# board-forblock.net
KiCad netlist of a schematic drawn in EAGLE
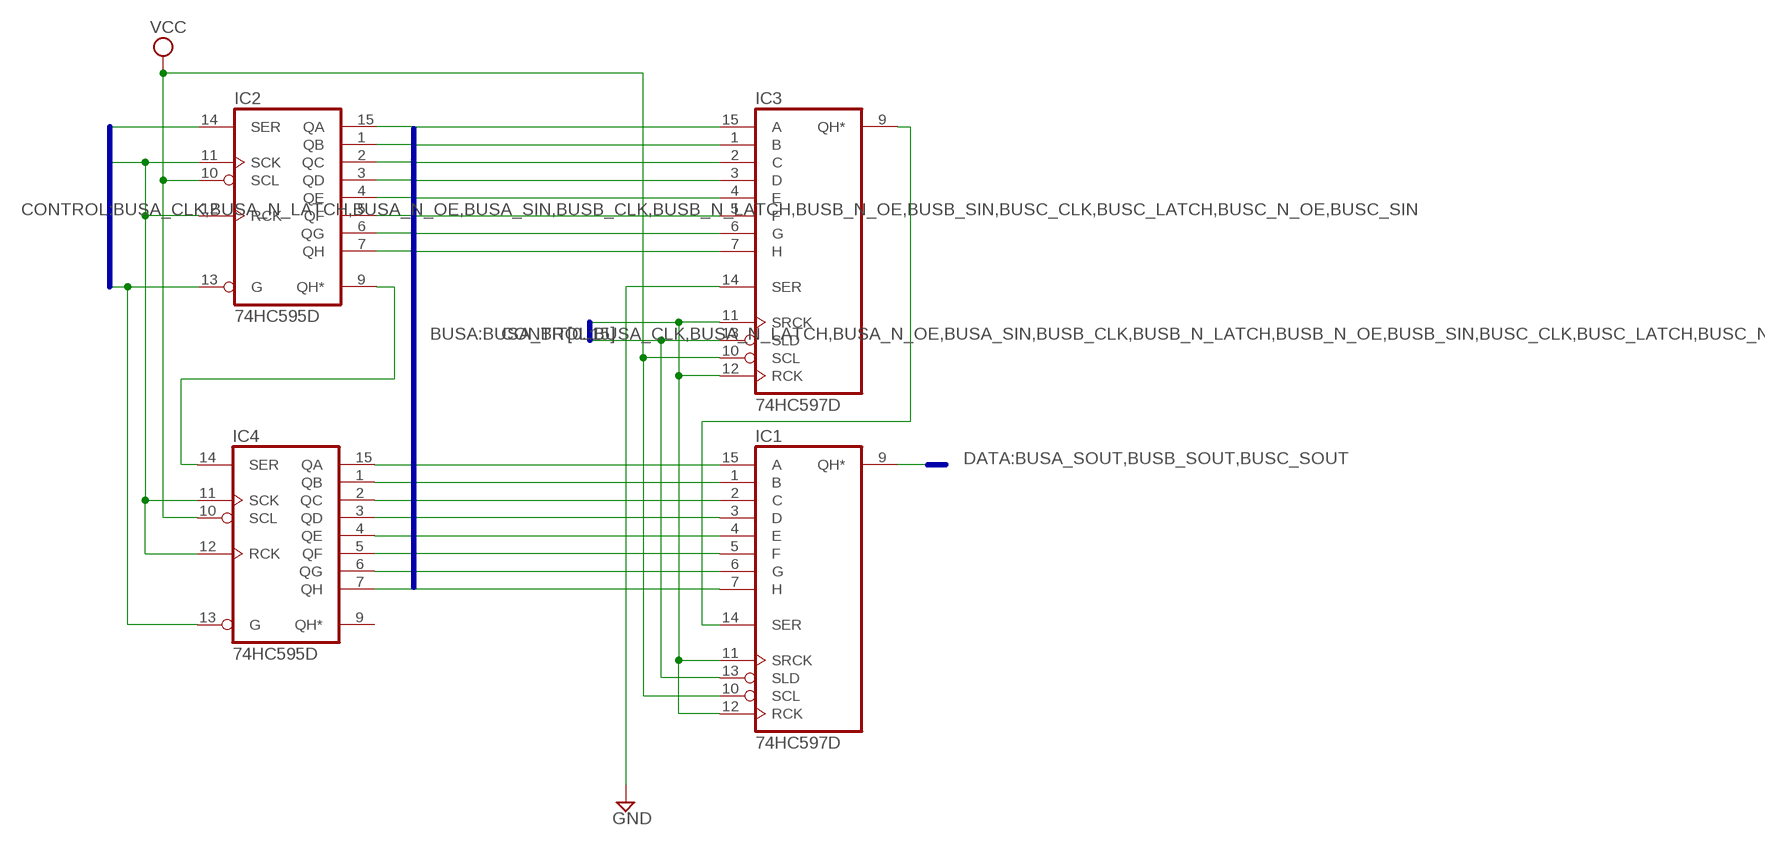
[diagram p0: schematic, sheet 1]

(export (version "E")
  (design (tool "Eeschema 10.0.6"))
  (components
    (comp (ref "IC1")
      (value "74HC597D")
      (footprint "eagle-import:SO16")
      (libsource (lib "eagle-import") (part "74597DHC"))
    )
    (comp (ref "IC2")
      (value "74HC595D")
      (footprint "eagle-import:SO16")
      (libsource (lib "eagle-import") (part "74595DHC"))
    )
    (comp (ref "IC3")
      (value "74HC597D")
      (footprint "eagle-import:SO16")
      (libsource (lib "eagle-import") (part "74597DHC"))
    )
    (comp (ref "IC4")
      (value "74HC595D")
      (footprint "eagle-import:SO16")
      (libsource (lib "eagle-import") (part "74595DHC"))
    )
  )
  (nets
    (net (code "33") (name "/BUSA_BIT0") (class "Default")
      (node (ref "IC2") (pin "15") (pinfunction "QA_15") (pintype "tri_state"))
      (node (ref "IC3") (pin "15") (pinfunction "A_15") (pintype "input"))
    )
    (net (code "34") (name "/BUSA_BIT1") (class "Default")
      (node (ref "IC2") (pin "1") (pinfunction "QB_1") (pintype "tri_state"))
      (node (ref "IC3") (pin "1") (pinfunction "B_1") (pintype "input"))
    )
    (net (code "35") (name "/BUSA_BIT2") (class "Default")
      (node (ref "IC2") (pin "2") (pinfunction "QC_2") (pintype "tri_state"))
      (node (ref "IC3") (pin "2") (pinfunction "C_2") (pintype "input"))
    )
    (net (code "36") (name "/BUSA_BIT3") (class "Default")
      (node (ref "IC2") (pin "3") (pinfunction "QD_3") (pintype "tri_state"))
      (node (ref "IC3") (pin "3") (pinfunction "D_3") (pintype "input"))
    )
    (net (code "37") (name "/BUSA_BIT4") (class "Default")
      (node (ref "IC2") (pin "4") (pinfunction "QE_4") (pintype "tri_state"))
      (node (ref "IC3") (pin "4") (pinfunction "E_4") (pintype "input"))
    )
    (net (code "38") (name "/BUSA_BIT5") (class "Default")
      (node (ref "IC2") (pin "5") (pinfunction "QF_5") (pintype "tri_state"))
      (node (ref "IC3") (pin "5") (pinfunction "F_5") (pintype "input"))
    )
    (net (code "39") (name "/BUSA_BIT6") (class "Default")
      (node (ref "IC2") (pin "6") (pinfunction "QG_6") (pintype "tri_state"))
      (node (ref "IC3") (pin "6") (pinfunction "G_6") (pintype "input"))
    )
    (net (code "40") (name "/BUSA_BIT7") (class "Default")
      (node (ref "IC2") (pin "7") (pinfunction "QH_7") (pintype "tri_state"))
      (node (ref "IC3") (pin "7") (pinfunction "H_7") (pintype "input"))
    )
    (net (code "41") (name "/BUSA_CLK") (class "Default")
      (node (ref "IC1") (pin "11") (pinfunction "SRCK_11") (pintype "input"))
      (node (ref "IC1") (pin "12") (pinfunction "RCK_12") (pintype "input"))
      (node (ref "IC2") (pin "11") (pinfunction "SCK_11") (pintype "input"))
      (node (ref "IC2") (pin "12") (pinfunction "RCK_12") (pintype "input"))
      (node (ref "IC3") (pin "11") (pinfunction "SRCK_11") (pintype "input"))
      (node (ref "IC3") (pin "12") (pinfunction "RCK_12") (pintype "input"))
      (node (ref "IC4") (pin "11") (pinfunction "SCK_11") (pintype "input"))
      (node (ref "IC4") (pin "12") (pinfunction "RCK_12") (pintype "input"))
    )
    (net (code "42") (name "/{CONTROL:BUSA_CLK BUSA_N_LATCH BUSA_N_OE BUSA_SIN BUSB_CLK BUSB_N_LATCH BUSB_N_OE BUSB_SIN BUSC_CLK BUSC_LATCH BUSC_N_OE BUSC_SIN}") (class "Default")
      (node (ref "IC1") (pin "13") (pinfunction "SLD_13") (pintype "input"))
      (node (ref "IC3") (pin "13") (pinfunction "SLD_13") (pintype "input"))
    )
    (net (code "44") (name "GND") (class "Default")
      (node (ref "IC3") (pin "14") (pinfunction "SER_14") (pintype "input"))
    )
    (net (code "45") (name "Net-(IC1A-A)") (class "Default")
      (node (ref "IC1") (pin "15") (pinfunction "A_15") (pintype "input"))
      (node (ref "IC4") (pin "15") (pinfunction "QA_15") (pintype "tri_state"))
    )
    (net (code "46") (name "Net-(IC1A-B)") (class "Default")
      (node (ref "IC1") (pin "1") (pinfunction "B_1") (pintype "input"))
      (node (ref "IC4") (pin "1") (pinfunction "QB_1") (pintype "tri_state"))
    )
    (net (code "47") (name "Net-(IC1A-C)") (class "Default")
      (node (ref "IC1") (pin "2") (pinfunction "C_2") (pintype "input"))
      (node (ref "IC4") (pin "2") (pinfunction "QC_2") (pintype "tri_state"))
    )
    (net (code "48") (name "Net-(IC1A-D)") (class "Default")
      (node (ref "IC1") (pin "3") (pinfunction "D_3") (pintype "input"))
      (node (ref "IC4") (pin "3") (pinfunction "QD_3") (pintype "tri_state"))
    )
    (net (code "49") (name "Net-(IC1A-E)") (class "Default")
      (node (ref "IC1") (pin "4") (pinfunction "E_4") (pintype "input"))
      (node (ref "IC4") (pin "4") (pinfunction "QE_4") (pintype "tri_state"))
    )
    (net (code "50") (name "Net-(IC1A-F)") (class "Default")
      (node (ref "IC1") (pin "5") (pinfunction "F_5") (pintype "input"))
      (node (ref "IC4") (pin "5") (pinfunction "QF_5") (pintype "tri_state"))
    )
    (net (code "51") (name "Net-(IC1A-G)") (class "Default")
      (node (ref "IC1") (pin "6") (pinfunction "G_6") (pintype "input"))
      (node (ref "IC4") (pin "6") (pinfunction "QG_6") (pintype "tri_state"))
    )
    (net (code "52") (name "Net-(IC1A-H)") (class "Default")
      (node (ref "IC1") (pin "7") (pinfunction "H_7") (pintype "input"))
      (node (ref "IC4") (pin "7") (pinfunction "QH_7") (pintype "tri_state"))
    )
    (net (code "53") (name "Net-(IC1A-SER)") (class "Default")
      (node (ref "IC1") (pin "14") (pinfunction "SER_14") (pintype "input"))
      (node (ref "IC3") (pin "9") (pinfunction "QH*_9") (pintype "output"))
    )
    (net (code "54") (name "Net-(IC2A-G)") (class "Default")
      (node (ref "IC2") (pin "13") (pinfunction "G_13") (pintype "input"))
      (node (ref "IC4") (pin "13") (pinfunction "G_13") (pintype "input"))
    )
    (net (code "55") (name "Net-(IC2A-QH*)") (class "Default")
      (node (ref "IC2") (pin "9") (pinfunction "QH*_9") (pintype "tri_state"))
      (node (ref "IC4") (pin "14") (pinfunction "SER_14") (pintype "input"))
    )
    (net (code "56") (name "VCC") (class "Default")
      (node (ref "IC1") (pin "10") (pinfunction "SCL_10") (pintype "input"))
      (node (ref "IC2") (pin "10") (pinfunction "SCL_10") (pintype "input"))
      (node (ref "IC3") (pin "10") (pinfunction "SCL_10") (pintype "input"))
      (node (ref "IC4") (pin "10") (pinfunction "SCL_10") (pintype "input"))
    )
    (net (code "57") (name "unconnected-(IC1A-QH*-Pad9)") (class "Default")
      (node (ref "IC1") (pin "9") (pinfunction "QH*_9") (pintype "output"))
    )
    (net (code "58") (name "unconnected-(IC2A-SER-Pad14)") (class "Default")
      (node (ref "IC2") (pin "14") (pinfunction "SER_14") (pintype "input"))
    )
    (net (code "59") (name "unconnected-(IC4A-QH*-Pad9)") (class "Default")
      (node (ref "IC4") (pin "9") (pinfunction "QH*_9") (pintype "tri_state"))
    )
  )
)
